# right_revision1_2.net
KiCad netlist of a schematic drawn in EAGLE
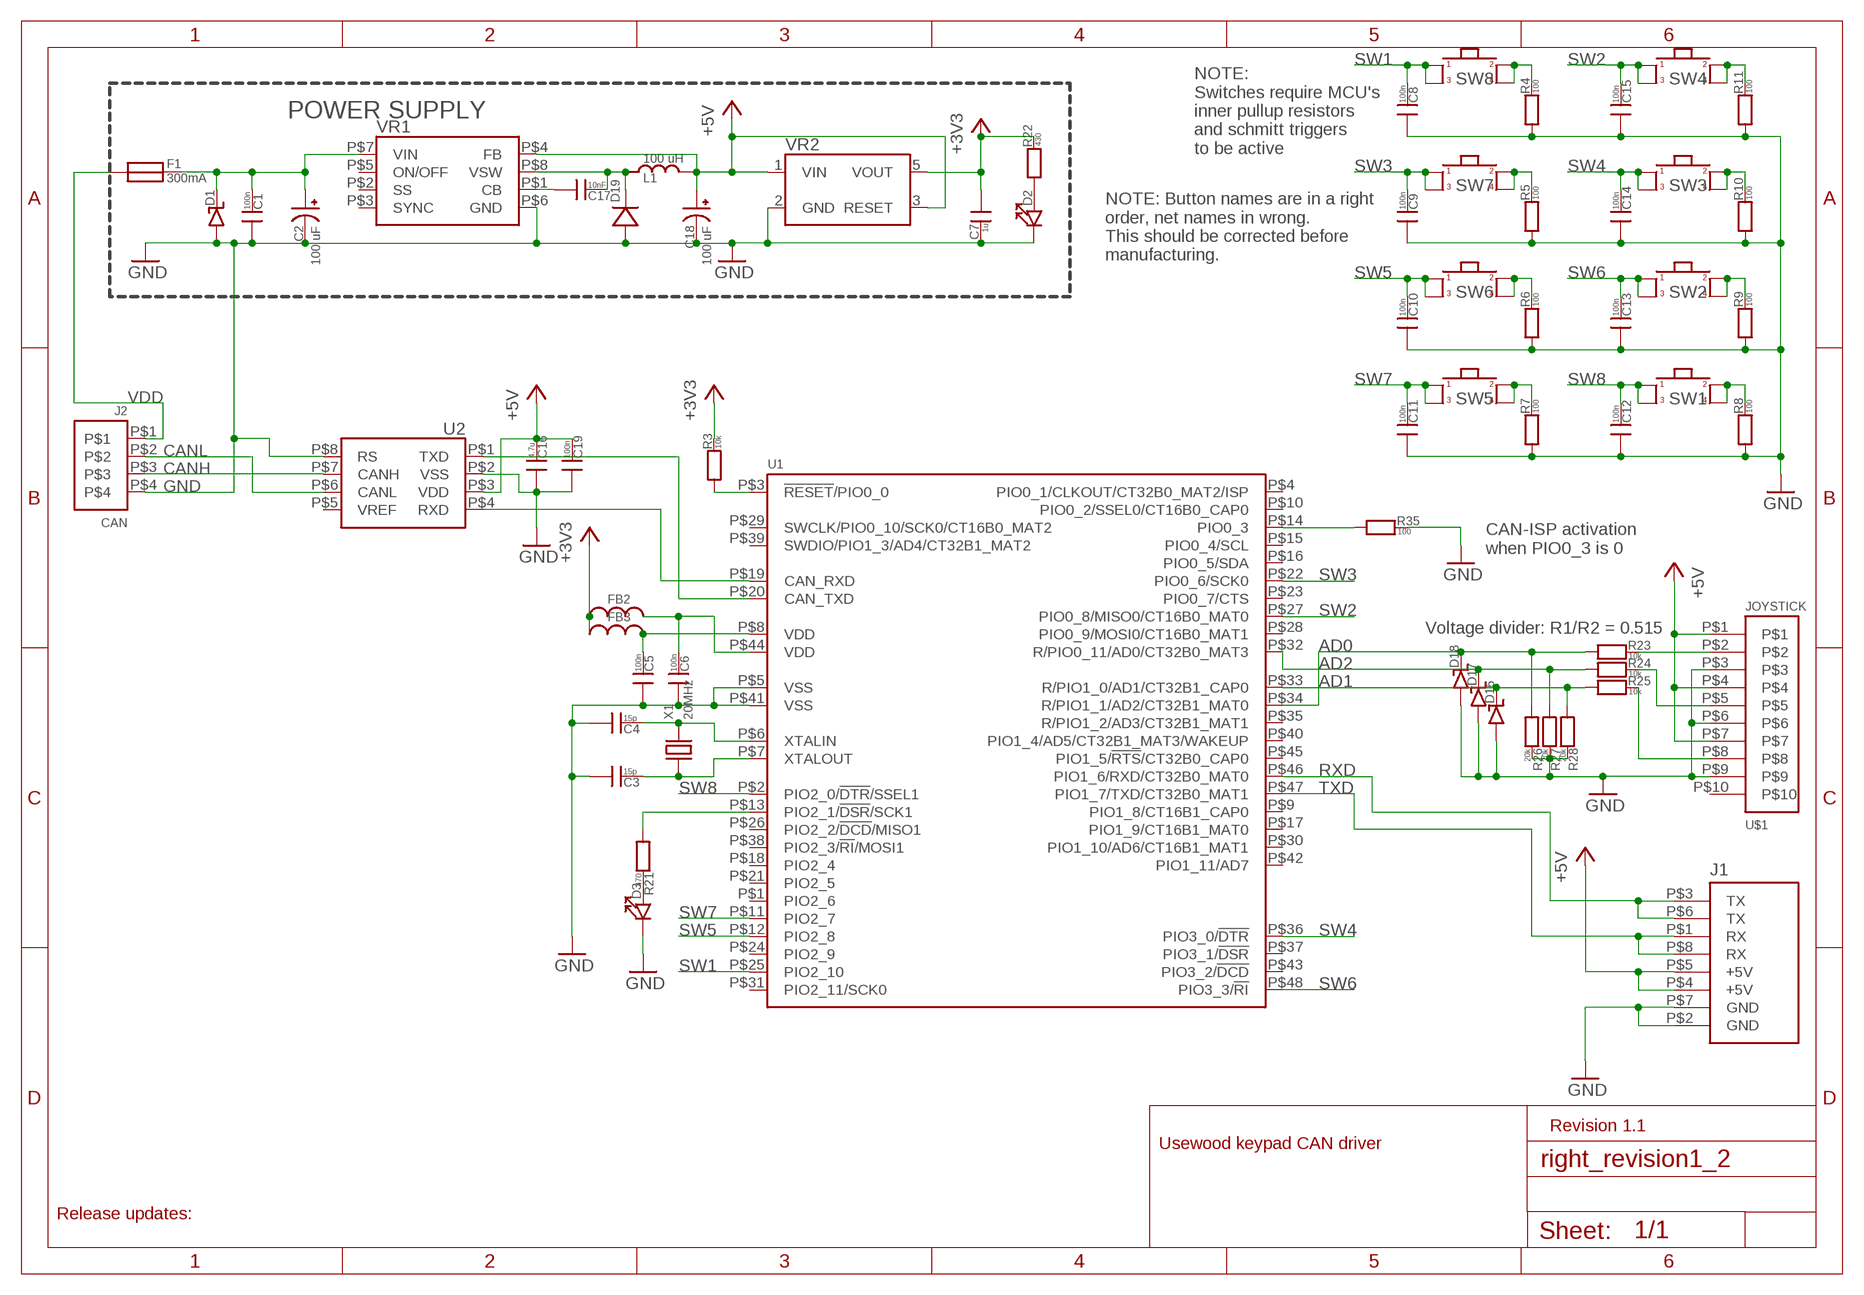
[diagram p0: schematic, sheet 1]

(export (version "E")
  (design (tool "Eeschema 10.0.6"))
  (components
    (comp (ref "C1")
      (value "100n")
      (footprint "eagle-import:0603_SILKSCREEN")
      (libsource (lib "eagle-import") (part "CAP0603_SILKSCREEN"))
    )
    (comp (ref "C2")
      (value "100 uF")
      (footprint "eagle-import:CAP_POL_SMD_10X10X10MM")
      (libsource (lib "eagle-import") (part "CAP_POLSMD_10X10X10MM"))
    )
    (comp (ref "C3")
      (value "15p")
      (footprint "eagle-import:0603_SILKSCREEN")
      (libsource (lib "eagle-import") (part "CAP0603_SILKSCREEN"))
    )
    (comp (ref "C4")
      (value "15p")
      (footprint "eagle-import:0603_SILKSCREEN")
      (libsource (lib "eagle-import") (part "CAP0603_SILKSCREEN"))
    )
    (comp (ref "C5")
      (value "100n")
      (footprint "eagle-import:0603_SILKSCREEN")
      (libsource (lib "eagle-import") (part "CAP0603_SILKSCREEN"))
    )
    (comp (ref "C6")
      (value "100n")
      (footprint "eagle-import:0603_SILKSCREEN")
      (libsource (lib "eagle-import") (part "CAP0603_SILKSCREEN"))
    )
    (comp (ref "C7")
      (value "1u")
      (footprint "eagle-import:0603_SILKSCREEN")
      (libsource (lib "eagle-import") (part "CAP0603_SILKSCREEN"))
    )
    (comp (ref "C8")
      (value "100n")
      (footprint "eagle-import:0603_SILKSCREEN")
      (libsource (lib "eagle-import") (part "CAP0603_SILKSCREEN"))
    )
    (comp (ref "C9")
      (value "100n")
      (footprint "eagle-import:0603_SILKSCREEN")
      (libsource (lib "eagle-import") (part "CAP0603_SILKSCREEN"))
    )
    (comp (ref "C10")
      (value "100n")
      (footprint "eagle-import:0603_SILKSCREEN")
      (libsource (lib "eagle-import") (part "CAP0603_SILKSCREEN"))
    )
    (comp (ref "C11")
      (value "100n")
      (footprint "eagle-import:0603_SILKSCREEN")
      (libsource (lib "eagle-import") (part "CAP0603_SILKSCREEN"))
    )
    (comp (ref "C12")
      (value "100n")
      (footprint "eagle-import:0603_SILKSCREEN")
      (libsource (lib "eagle-import") (part "CAP0603_SILKSCREEN"))
    )
    (comp (ref "C13")
      (value "100n")
      (footprint "eagle-import:0603_SILKSCREEN")
      (libsource (lib "eagle-import") (part "CAP0603_SILKSCREEN"))
    )
    (comp (ref "C14")
      (value "100n")
      (footprint "eagle-import:0603_SILKSCREEN")
      (libsource (lib "eagle-import") (part "CAP0603_SILKSCREEN"))
    )
    (comp (ref "C15")
      (value "100n")
      (footprint "eagle-import:0603_SILKSCREEN")
      (libsource (lib "eagle-import") (part "CAP0603_SILKSCREEN"))
    )
    (comp (ref "C16")
      (value "4.7u")
      (footprint "eagle-import:0603_SILKSCREEN")
      (libsource (lib "eagle-import") (part "CAP0603_SILKSCREEN"))
    )
    (comp (ref "C17")
      (value "10nF")
      (footprint "eagle-import:0603_SILKSCREEN")
      (libsource (lib "eagle-import") (part "CAP0603_SILKSCREEN"))
    )
    (comp (ref "C18")
      (value "100 uF")
      (footprint "eagle-import:CAP_POL_SMD_10X10X10MM")
      (libsource (lib "eagle-import") (part "CAP_POLSMD_10X10X10MM"))
    )
    (comp (ref "C19")
      (value "100n")
      (footprint "eagle-import:0603_SILKSCREEN")
      (libsource (lib "eagle-import") (part "CAP0603_SILKSCREEN"))
    )
    (comp (ref "D1")
      (value "DIODE_TVSDO-214AA")
      (footprint "eagle-import:DO-214AB")
      (libsource (lib "eagle-import") (part "DIODE_TVSDO-214AA"))
    )
    (comp (ref "D2")
      (value "LED0603_SILKSCREEN")
      (footprint "eagle-import:0603_SILKSCREEN")
      (libsource (lib "eagle-import") (part "LED0603_SILKSCREEN"))
    )
    (comp (ref "D3")
      (value "LED0603_SILKSCREEN")
      (footprint "eagle-import:0603_SILKSCREEN")
      (libsource (lib "eagle-import") (part "LED0603_SILKSCREEN"))
    )
    (comp (ref "D16")
      (value "DIODE_ZENERSDO123")
      (footprint "eagle-import:SOD123")
      (libsource (lib "eagle-import") (part "DIODE_ZENERSDO123"))
    )
    (comp (ref "D17")
      (value "DIODE_ZENERSDO123")
      (footprint "eagle-import:SOD123")
      (libsource (lib "eagle-import") (part "DIODE_ZENERSDO123"))
    )
    (comp (ref "D18")
      (value "DIODE_ZENERSDO123")
      (footprint "eagle-import:SOD123")
      (libsource (lib "eagle-import") (part "DIODE_ZENERSDO123"))
    )
    (comp (ref "D19")
      (value "DIODEDO219AB")
      (footprint "eagle-import:DO219AB")
      (libsource (lib "eagle-import") (part "DIODEDO219AB"))
    )
    (comp (ref "F1")
      (value "300mA")
      (footprint "eagle-import:FUSE_100MA")
      (libsource (lib "eagle-import") (part "FUSE100MA"))
    )
    (comp (ref "FB2")
      (value "FERRITE0603_SILKSCREEN")
      (footprint "eagle-import:0603_SILKSCREEN")
      (libsource (lib "eagle-import") (part "FERRITE0603_SILKSCREEN"))
    )
    (comp (ref "FB3")
      (value "FERRITE0603_SILKSCREEN")
      (footprint "eagle-import:0603_SILKSCREEN")
      (libsource (lib "eagle-import") (part "FERRITE0603_SILKSCREEN"))
    )
    (comp (ref "J1")
      (value "HEADER_USART_2_TH")
      (footprint "eagle-import:HEADER_USART_2_TH")
      (libsource (lib "eagle-import") (part "HEADER_USART_2_TH"))
    )
    (comp (ref "J2")
      (value "CAN")
      (footprint "eagle-import:MOLEX_MICRO-FIT_4WAY")
      (libsource (lib "eagle-import") (part "MOLEX_MICRO-FIT_4WAYTH"))
    )
    (comp (ref "L1")
      (value "100 uH")
      (footprint "eagle-import:INDUCTOR_BOURNS_10X13X5MM")
      (libsource (lib "eagle-import") (part "INDUCTORBOURNS_10X13X5MM"))
    )
    (comp (ref "R3")
      (value "10k")
      (footprint "eagle-import:0603_SILKSCREEN")
      (libsource (lib "eagle-import") (part "RES0604_SILKSCREEN"))
    )
    (comp (ref "R4")
      (value "100")
      (footprint "eagle-import:0603_SILKSCREEN")
      (libsource (lib "eagle-import") (part "RES0604_SILKSCREEN"))
    )
    (comp (ref "R5")
      (value "100")
      (footprint "eagle-import:0603_SILKSCREEN")
      (libsource (lib "eagle-import") (part "RES0604_SILKSCREEN"))
    )
    (comp (ref "R6")
      (value "100")
      (footprint "eagle-import:0603_SILKSCREEN")
      (libsource (lib "eagle-import") (part "RES0604_SILKSCREEN"))
    )
    (comp (ref "R7")
      (value "100")
      (footprint "eagle-import:0603_SILKSCREEN")
      (libsource (lib "eagle-import") (part "RES0604_SILKSCREEN"))
    )
    (comp (ref "R8")
      (value "100")
      (footprint "eagle-import:0603_SILKSCREEN")
      (libsource (lib "eagle-import") (part "RES0604_SILKSCREEN"))
    )
    (comp (ref "R9")
      (value "100")
      (footprint "eagle-import:0603_SILKSCREEN")
      (libsource (lib "eagle-import") (part "RES0604_SILKSCREEN"))
    )
    (comp (ref "R10")
      (value "100")
      (footprint "eagle-import:0603_SILKSCREEN")
      (libsource (lib "eagle-import") (part "RES0604_SILKSCREEN"))
    )
    (comp (ref "R11")
      (value "100")
      (footprint "eagle-import:0603_SILKSCREEN")
      (libsource (lib "eagle-import") (part "RES0604_SILKSCREEN"))
    )
    (comp (ref "R21")
      (value "470")
      (footprint "eagle-import:0603_SILKSCREEN")
      (libsource (lib "eagle-import") (part "RES0604_SILKSCREEN"))
    )
    (comp (ref "R22")
      (value "430")
      (footprint "eagle-import:0603_SILKSCREEN")
      (libsource (lib "eagle-import") (part "RES0604_SILKSCREEN"))
    )
    (comp (ref "R23")
      (value "10k")
      (footprint "eagle-import:0603_SILKSCREEN")
      (libsource (lib "eagle-import") (part "RES0604_SILKSCREEN"))
    )
    (comp (ref "R24")
      (value "10k")
      (footprint "eagle-import:0603_SILKSCREEN")
      (libsource (lib "eagle-import") (part "RES0604_SILKSCREEN"))
    )
    (comp (ref "R25")
      (value "10k")
      (footprint "eagle-import:0603_SILKSCREEN")
      (libsource (lib "eagle-import") (part "RES0604_SILKSCREEN"))
    )
    (comp (ref "R26")
      (value "20k")
      (footprint "eagle-import:0603_SILKSCREEN")
      (libsource (lib "eagle-import") (part "RES0604_SILKSCREEN"))
    )
    (comp (ref "R27")
      (value "20k")
      (footprint "eagle-import:0603_SILKSCREEN")
      (libsource (lib "eagle-import") (part "RES0604_SILKSCREEN"))
    )
    (comp (ref "R28")
      (value "20k")
      (footprint "eagle-import:0603_SILKSCREEN")
      (libsource (lib "eagle-import") (part "RES0604_SILKSCREEN"))
    )
    (comp (ref "R35")
      (value "100")
      (footprint "eagle-import:0603_SILKSCREEN")
      (libsource (lib "eagle-import") (part "RES0604_SILKSCREEN"))
    )
    (comp (ref "SW1")
      (value "SWITCH12X12MM_CENTER_HOLE")
      (footprint "eagle-import:SWITCH_12X12MM_CENTER_HOLE")
      (libsource (lib "eagle-import") (part "SWITCH12X12MM_CENTER_HOLE"))
    )
    (comp (ref "SW2")
      (value "SWITCH12X12MM_CENTER_HOLE")
      (footprint "eagle-import:SWITCH_12X12MM_CENTER_HOLE")
      (libsource (lib "eagle-import") (part "SWITCH12X12MM_CENTER_HOLE"))
    )
    (comp (ref "SW3")
      (value "SWITCH12X12MM_CENTER_HOLE")
      (footprint "eagle-import:SWITCH_12X12MM_CENTER_HOLE")
      (libsource (lib "eagle-import") (part "SWITCH12X12MM_CENTER_HOLE"))
    )
    (comp (ref "SW4")
      (value "SWITCH12X12MM_CENTER_HOLE")
      (footprint "eagle-import:SWITCH_12X12MM_CENTER_HOLE")
      (libsource (lib "eagle-import") (part "SWITCH12X12MM_CENTER_HOLE"))
    )
    (comp (ref "SW5")
      (value "SWITCH12X12MM_CENTER_HOLE")
      (footprint "eagle-import:SWITCH_12X12MM_CENTER_HOLE")
      (libsource (lib "eagle-import") (part "SWITCH12X12MM_CENTER_HOLE"))
    )
    (comp (ref "SW6")
      (value "SWITCH12X12MM_CENTER_HOLE")
      (footprint "eagle-import:SWITCH_12X12MM_CENTER_HOLE")
      (libsource (lib "eagle-import") (part "SWITCH12X12MM_CENTER_HOLE"))
    )
    (comp (ref "SW7")
      (value "SWITCH12X12MM_CENTER_HOLE")
      (footprint "eagle-import:SWITCH_12X12MM_CENTER_HOLE")
      (libsource (lib "eagle-import") (part "SWITCH12X12MM_CENTER_HOLE"))
    )
    (comp (ref "SW8")
      (value "SWITCH12X12MM_CENTER_HOLE")
      (footprint "eagle-import:SWITCH_12X12MM_CENTER_HOLE")
      (libsource (lib "eagle-import") (part "SWITCH12X12MM_CENTER_HOLE"))
    )
    (comp (ref "U$1")
      (value "JOYSTICK")
      (footprint "eagle-import:MOLEX-MICRO-FIT_10WAY")
      (libsource (lib "eagle-import") (part "MOLEX_MICRO-FIT_10WAYTH"))
    )
    (comp (ref "U1")
      (value "LPC11C14_QFP48")
      (footprint "eagle-import:QFP48")
      (libsource (lib "eagle-import") (part "LPC11C14_QFP48"))
    )
    (comp (ref "U2")
      (value "MCP2551_SOIC8")
      (footprint "eagle-import:SOIC8")
      (libsource (lib "eagle-import") (part "MCP2551_SOIC8"))
    )
    (comp (ref "VR1")
      (value "LM2671SOIC8")
      (footprint "eagle-import:SOIC8")
      (libsource (lib "eagle-import") (part "LM2671SOIC8"))
    )
    (comp (ref "VR2")
      (value "LP2985SOP5")
      (footprint "eagle-import:SOP5")
      (libsource (lib "eagle-import") (part "LP2985SOP5"))
    )
    (comp (ref "X1")
      (value "20MHz")
      (footprint "eagle-import:XTAL_SMD_5X3.2")
      (libsource (lib "eagle-import") (part "XTALSMD_5X3.2"))
    )
  )
  (nets
    (net (code "1") (name "+3V3") (class "Default")
      (node (ref "C7") (pin "0") (pinfunction "P$1_0") (pintype "bidirectional"))
      (node (ref "FB2") (pin "0") (pinfunction "P$1_0") (pintype "bidirectional"))
      (node (ref "FB3") (pin "0") (pinfunction "P$1_0") (pintype "bidirectional"))
      (node (ref "R22") (pin "1") (pinfunction "P$2_1") (pintype "bidirectional"))
      (node (ref "R3") (pin "1") (pinfunction "P$2_1") (pintype "bidirectional"))
      (node (ref "VR2") (pin "5") (pinfunction "VOUT_5") (pintype "bidirectional"))
    )
    (net (code "2") (name "+5V") (class "Default")
      (node (ref "C16") (pin "1") (pinfunction "P$2_1") (pintype "bidirectional"))
      (node (ref "C18") (pin "+") (pinfunction "+_+") (pintype "bidirectional"))
      (node (ref "C19") (pin "1") (pinfunction "P$2_1") (pintype "bidirectional"))
      (node (ref "J1") (pin "P$4") (pinfunction "+5V_P$4") (pintype "bidirectional"))
      (node (ref "J1") (pin "P$5") (pinfunction "+5V_P$5") (pintype "bidirectional"))
      (node (ref "L1") (pin "P$2") (pinfunction "P$2_P$2") (pintype "bidirectional"))
      (node (ref "U$1") (pin "P$1") (pinfunction "P$1_P$1") (pintype "bidirectional"))
      (node (ref "U$1") (pin "P$4") (pinfunction "P$4_P$4") (pintype "bidirectional"))
      (node (ref "U$1") (pin "P$7") (pinfunction "P$7_P$7") (pintype "bidirectional"))
      (node (ref "U2") (pin "P$3") (pinfunction "VDD_P$3") (pintype "bidirectional"))
      (node (ref "VR1") (pin "P$4") (pinfunction "FB_P$4") (pintype "bidirectional"))
      (node (ref "VR2") (pin "1") (pinfunction "VIN_1") (pintype "bidirectional"))
      (node (ref "VR2") (pin "3") (pinfunction "RESET_3") (pintype "bidirectional"))
    )
    (net (code "3") (name "/AD0") (class "Default")
      (node (ref "D18") (pin "P$2") (pinfunction "N_P$2") (pintype "bidirectional"))
      (node (ref "R23") (pin "0") (pinfunction "P$1_0") (pintype "bidirectional"))
      (node (ref "R26") (pin "0") (pinfunction "P$1_0") (pintype "bidirectional"))
      (node (ref "U1") (pin "P$34") (pinfunction "R/PIO1_1/AD2/CT32B1_MAT0_P$34") (pintype "bidirectional"))
    )
    (net (code "4") (name "/AD1") (class "Default")
      (node (ref "D16") (pin "P$2") (pinfunction "N_P$2") (pintype "bidirectional"))
      (node (ref "R25") (pin "0") (pinfunction "P$1_0") (pintype "bidirectional"))
      (node (ref "R28") (pin "0") (pinfunction "P$1_0") (pintype "bidirectional"))
      (node (ref "U1") (pin "P$33") (pinfunction "R/PIO1_0/AD1/CT32B1_CAP0_P$33") (pintype "bidirectional"))
    )
    (net (code "5") (name "/AD2") (class "Default")
      (node (ref "D17") (pin "P$2") (pinfunction "N_P$2") (pintype "bidirectional"))
      (node (ref "R24") (pin "0") (pinfunction "P$1_0") (pintype "bidirectional"))
      (node (ref "R27") (pin "0") (pinfunction "P$1_0") (pintype "bidirectional"))
      (node (ref "U1") (pin "P$32") (pinfunction "R/PIO0_11/AD0/CT32B0_MAT3_P$32") (pintype "bidirectional"))
    )
    (net (code "6") (name "/CANH") (class "Default")
      (node (ref "J2") (pin "P$3") (pinfunction "P$3_P$3") (pintype "bidirectional"))
      (node (ref "U2") (pin "P$7") (pinfunction "CANH_P$7") (pintype "bidirectional"))
    )
    (net (code "7") (name "/CANL") (class "Default")
      (node (ref "J2") (pin "P$2") (pinfunction "P$2_P$2") (pintype "bidirectional"))
      (node (ref "U2") (pin "P$6") (pinfunction "CANL_P$6") (pintype "bidirectional"))
    )
    (net (code "8") (name "/RXD") (class "Default")
      (node (ref "J1") (pin "P$3") (pinfunction "TX_P$3") (pintype "bidirectional"))
      (node (ref "J1") (pin "P$6") (pinfunction "TX_P$6") (pintype "bidirectional"))
      (node (ref "U1") (pin "P$46") (pinfunction "PIO1_6/RXD/CT32B0_MAT0_P$46") (pintype "bidirectional"))
    )
    (net (code "9") (name "/SW1") (class "Default")
      (node (ref "C8") (pin "1") (pinfunction "P$2_1") (pintype "bidirectional"))
      (node (ref "SW8") (pin "P$1") (pinfunction "P$1_P$1") (pintype "bidirectional"))
      (node (ref "SW8") (pin "P$2") (pinfunction "P$3_P$2") (pintype "bidirectional"))
      (node (ref "U1") (pin "P$25") (pinfunction "PIO2_10_P$25") (pintype "bidirectional"))
    )
    (net (code "10") (name "/SW2") (class "Default")
      (node (ref "C15") (pin "1") (pinfunction "P$2_1") (pintype "bidirectional"))
      (node (ref "SW4") (pin "P$1") (pinfunction "P$1_P$1") (pintype "bidirectional"))
      (node (ref "SW4") (pin "P$2") (pinfunction "P$3_P$2") (pintype "bidirectional"))
      (node (ref "U1") (pin "P$27") (pinfunction "PIO0_8/MISO0/CT16B0_MAT0_P$27") (pintype "bidirectional"))
    )
    (net (code "11") (name "/SW3") (class "Default")
      (node (ref "C9") (pin "1") (pinfunction "P$2_1") (pintype "bidirectional"))
      (node (ref "SW7") (pin "P$1") (pinfunction "P$1_P$1") (pintype "bidirectional"))
      (node (ref "SW7") (pin "P$2") (pinfunction "P$3_P$2") (pintype "bidirectional"))
      (node (ref "U1") (pin "P$22") (pinfunction "PIO0_6/SCK0_P$22") (pintype "bidirectional"))
    )
    (net (code "12") (name "/SW4") (class "Default")
      (node (ref "C14") (pin "1") (pinfunction "P$2_1") (pintype "bidirectional"))
      (node (ref "SW3") (pin "P$1") (pinfunction "P$1_P$1") (pintype "bidirectional"))
      (node (ref "SW3") (pin "P$2") (pinfunction "P$3_P$2") (pintype "bidirectional"))
      (node (ref "U1") (pin "P$36") (pinfunction "PIO3_0/~{DTR}_P$36") (pintype "bidirectional"))
    )
    (net (code "13") (name "/SW5") (class "Default")
      (node (ref "C10") (pin "1") (pinfunction "P$2_1") (pintype "bidirectional"))
      (node (ref "SW6") (pin "P$1") (pinfunction "P$1_P$1") (pintype "bidirectional"))
      (node (ref "SW6") (pin "P$2") (pinfunction "P$3_P$2") (pintype "bidirectional"))
      (node (ref "U1") (pin "P$12") (pinfunction "PIO2_8_P$12") (pintype "bidirectional"))
    )
    (net (code "14") (name "/SW6") (class "Default")
      (node (ref "C13") (pin "1") (pinfunction "P$2_1") (pintype "bidirectional"))
      (node (ref "SW2") (pin "P$1") (pinfunction "P$1_P$1") (pintype "bidirectional"))
      (node (ref "SW2") (pin "P$2") (pinfunction "P$3_P$2") (pintype "bidirectional"))
      (node (ref "U1") (pin "P$48") (pinfunction "PIO3_3/~{RI}_P$48") (pintype "bidirectional"))
    )
    (net (code "15") (name "/SW7") (class "Default")
      (node (ref "C11") (pin "1") (pinfunction "P$2_1") (pintype "bidirectional"))
      (node (ref "SW5") (pin "P$1") (pinfunction "P$1_P$1") (pintype "bidirectional"))
      (node (ref "SW5") (pin "P$2") (pinfunction "P$3_P$2") (pintype "bidirectional"))
      (node (ref "U1") (pin "P$11") (pinfunction "PIO2_7_P$11") (pintype "bidirectional"))
    )
    (net (code "16") (name "/SW8") (class "Default")
      (node (ref "C12") (pin "1") (pinfunction "P$2_1") (pintype "bidirectional"))
      (node (ref "SW1") (pin "P$1") (pinfunction "P$1_P$1") (pintype "bidirectional"))
      (node (ref "SW1") (pin "P$2") (pinfunction "P$3_P$2") (pintype "bidirectional"))
      (node (ref "U1") (pin "P$2") (pinfunction "PIO2_0/~{DTR}/SSEL1_P$2") (pintype "bidirectional"))
    )
    (net (code "17") (name "/TXD") (class "Default")
      (node (ref "J1") (pin "P$1") (pinfunction "RX_P$1") (pintype "bidirectional"))
      (node (ref "J1") (pin "P$8") (pinfunction "RX_P$8") (pintype "bidirectional"))
      (node (ref "U1") (pin "P$47") (pinfunction "PIO1_7/TXD/CT32B0_MAT1_P$47") (pintype "bidirectional"))
    )
    (net (code "18") (name "/VDD") (class "Default")
      (node (ref "F1") (pin "P$1") (pinfunction "P$1_P$1") (pintype "bidirectional"))
      (node (ref "J2") (pin "P$1") (pinfunction "P$1_P$1") (pintype "bidirectional"))
    )
    (net (code "19") (name "GND") (class "Default")
      (node (ref "C1") (pin "0") (pinfunction "P$1_0") (pintype "bidirectional"))
      (node (ref "C10") (pin "0") (pinfunction "P$1_0") (pintype "bidirectional"))
      (node (ref "C11") (pin "0") (pinfunction "P$1_0") (pintype "bidirectional"))
      (node (ref "C12") (pin "0") (pinfunction "P$1_0") (pintype "bidirectional"))
      (node (ref "C13") (pin "0") (pinfunction "P$1_0") (pintype "bidirectional"))
      (node (ref "C14") (pin "0") (pinfunction "P$1_0") (pintype "bidirectional"))
      (node (ref "C15") (pin "0") (pinfunction "P$1_0") (pintype "bidirectional"))
      (node (ref "C16") (pin "0") (pinfunction "P$1_0") (pintype "bidirectional"))
      (node (ref "C18") (pin "-") (pinfunction "-_-") (pintype "bidirectional"))
      (node (ref "C19") (pin "0") (pinfunction "P$1_0") (pintype "bidirectional"))
      (node (ref "C2") (pin "-") (pinfunction "-_-") (pintype "bidirectional"))
      (node (ref "C3") (pin "0") (pinfunction "P$1_0") (pintype "bidirectional"))
      (node (ref "C4") (pin "0") (pinfunction "P$1_0") (pintype "bidirectional"))
      (node (ref "C5") (pin "0") (pinfunction "P$1_0") (pintype "bidirectional"))
      (node (ref "C6") (pin "0") (pinfunction "P$1_0") (pintype "bidirectional"))
      (node (ref "C7") (pin "1") (pinfunction "P$2_1") (pintype "bidirectional"))
      (node (ref "C8") (pin "0") (pinfunction "P$1_0") (pintype "bidirectional"))
      (node (ref "C9") (pin "0") (pinfunction "P$1_0") (pintype "bidirectional"))
      (node (ref "D1") (pin "P$1") (pinfunction "P_P$1") (pintype "bidirectional"))
      (node (ref "D16") (pin "P$1") (pinfunction "P_P$1") (pintype "bidirectional"))
      (node (ref "D17") (pin "P$1") (pinfunction "P_P$1") (pintype "bidirectional"))
      (node (ref "D18") (pin "P$1") (pinfunction "P_P$1") (pintype "bidirectional"))
      (node (ref "D19") (pin "P$1") (pinfunction "P_P$1") (pintype "bidirectional"))
      (node (ref "D2") (pin "1") (pinfunction "1_1") (pintype "bidirectional"))
      (node (ref "D3") (pin "1") (pinfunction "1_1") (pintype "bidirectional"))
      (node (ref "J1") (pin "P$2") (pinfunction "GND_P$2") (pintype "bidirectional"))
      (node (ref "J1") (pin "P$7") (pinfunction "GND_P$7") (pintype "bidirectional"))
      (node (ref "J2") (pin "P$4") (pinfunction "P$4_P$4") (pintype "bidirectional"))
      (node (ref "R10") (pin "0") (pinfunction "P$1_0") (pintype "bidirectional"))
      (node (ref "R11") (pin "0") (pinfunction "P$1_0") (pintype "bidirectional"))
      (node (ref "R26") (pin "1") (pinfunction "P$2_1") (pintype "bidirectional"))
      (node (ref "R27") (pin "1") (pinfunction "P$2_1") (pintype "bidirectional"))
      (node (ref "R28") (pin "1") (pinfunction "P$2_1") (pintype "bidirectional"))
      (node (ref "R35") (pin "1") (pinfunction "P$2_1") (pintype "bidirectional"))
      (node (ref "R4") (pin "0") (pinfunction "P$1_0") (pintype "bidirectional"))
      (node (ref "R5") (pin "0") (pinfunction "P$1_0") (pintype "bidirectional"))
      (node (ref "R6") (pin "0") (pinfunction "P$1_0") (pintype "bidirectional"))
      (node (ref "R7") (pin "0") (pinfunction "P$1_0") (pintype "bidirectional"))
      (node (ref "R8") (pin "0") (pinfunction "P$1_0") (pintype "bidirectional"))
      (node (ref "R9") (pin "0") (pinfunction "P$1_0") (pintype "bidirectional"))
      (node (ref "U$1") (pin "P$3") (pinfunction "P$3_P$3") (pintype "bidirectional"))
      (node (ref "U$1") (pin "P$6") (pinfunction "P$6_P$6") (pintype "bidirectional"))
      (node (ref "U$1") (pin "P$9") (pinfunction "P$9_P$9") (pintype "bidirectional"))
      (node (ref "U1") (pin "P$41") (pinfunction "VSS_P$41") (pintype "bidirectional"))
      (node (ref "U1") (pin "P$5") (pinfunction "VSS_P$5") (pintype "bidirectional"))
      (node (ref "U2") (pin "P$2") (pinfunction "VSS_P$2") (pintype "bidirectional"))
      (node (ref "U2") (pin "P$8") (pinfunction "RS_P$8") (pintype "bidirectional"))
      (node (ref "VR1") (pin "P$6") (pinfunction "GND_P$6") (pintype "bidirectional"))
      (node (ref "VR2") (pin "2") (pinfunction "GND_2") (pintype "bidirectional"))
    )
    (net (code "20") (name "Net-(C1-P$2)") (class "Default")
      (node (ref "C1") (pin "1") (pinfunction "P$2_1") (pintype "bidirectional"))
      (node (ref "C2") (pin "+") (pinfunction "+_+") (pintype "bidirectional"))
      (node (ref "D1") (pin "P$2") (pinfunction "N_P$2") (pintype "bidirectional"))
      (node (ref "F1") (pin "P$2") (pinfunction "P$2_P$2") (pintype "bidirectional"))
      (node (ref "VR1") (pin "P$7") (pinfunction "VIN_P$7") (pintype "bidirectional"))
    )
    (net (code "21") (name "Net-(C3-P$2)") (class "Default")
      (node (ref "C3") (pin "1") (pinfunction "P$2_1") (pintype "bidirectional"))
      (node (ref "U1") (pin "P$7") (pinfunction "XTALOUT_P$7") (pintype "bidirectional"))
      (node (ref "X1") (pin "P$1") (pinfunction "P$1_P$1") (pintype "bidirectional"))
    )
    (net (code "22") (name "Net-(C4-P$2)") (class "Default")
      (node (ref "C4") (pin "1") (pinfunction "P$2_1") (pintype "bidirectional"))
      (node (ref "U1") (pin "P$6") (pinfunction "XTALIN_P$6") (pintype "bidirectional"))
      (node (ref "X1") (pin "P$2") (pinfunction "P$2_P$2") (pintype "bidirectional"))
    )
    (net (code "23") (name "Net-(C5-P$2)") (class "Default")
      (node (ref "C5") (pin "1") (pinfunction "P$2_1") (pintype "bidirectional"))
      (node (ref "FB3") (pin "1") (pinfunction "P$2_1") (pintype "bidirectional"))
      (node (ref "U1") (pin "P$8") (pinfunction "VDD_P$8") (pintype "bidirectional"))
    )
    (net (code "24") (name "Net-(C6-P$2)") (class "Default")
      (node (ref "C6") (pin "1") (pinfunction "P$2_1") (pintype "bidirectional"))
      (node (ref "FB2") (pin "1") (pinfunction "P$2_1") (pintype "bidirectional"))
      (node (ref "U1") (pin "P$44") (pinfunction "VDD_P$44") (pintype "bidirectional"))
    )
    (net (code "25") (name "Net-(C17-P$1)") (class "Default")
      (node (ref "C17") (pin "0") (pinfunction "P$1_0") (pintype "bidirectional"))
      (node (ref "VR1") (pin "P$1") (pinfunction "CB_P$1") (pintype "bidirectional"))
    )
    (net (code "26") (name "Net-(C17-P$2)") (class "Default")
      (node (ref "C17") (pin "1") (pinfunction "P$2_1") (pintype "bidirectional"))
      (node (ref "D19") (pin "P$2") (pinfunction "N_P$2") (pintype "bidirectional"))
      (node (ref "L1") (pin "P$1") (pinfunction "P$1_P$1") (pintype "bidirectional"))
      (node (ref "VR1") (pin "P$8") (pinfunction "VSW_P$8") (pintype "bidirectional"))
    )
    (net (code "27") (name "Net-(R3-P$1)") (class "Default")
      (node (ref "R3") (pin "0") (pinfunction "P$1_0") (pintype "bidirectional"))
      (node (ref "U1") (pin "P$3") (pinfunction "~{RESET}/PIO0_0_P$3") (pintype "bidirectional"))
    )
    (net (code "28") (name "Net-(R4-P$2)") (class "Default")
      (node (ref "R4") (pin "1") (pinfunction "P$2_1") (pintype "bidirectional"))
      (node (ref "SW8") (pin "P$3") (pinfunction "P$2_P$3") (pintype "bidirectional"))
      (node (ref "SW8") (pin "P$4") (pinfunction "P$4_P$4") (pintype "bidirectional"))
    )
    (net (code "29") (name "Net-(R5-P$2)") (class "Default")
      (node (ref "R5") (pin "1") (pinfunction "P$2_1") (pintype "bidirectional"))
      (node (ref "SW7") (pin "P$3") (pinfunction "P$2_P$3") (pintype "bidirectional"))
      (node (ref "SW7") (pin "P$4") (pinfunction "P$4_P$4") (pintype "bidirectional"))
    )
    (net (code "30") (name "Net-(R6-P$2)") (class "Default")
      (node (ref "R6") (pin "1") (pinfunction "P$2_1") (pintype "bidirectional"))
      (node (ref "SW6") (pin "P$3") (pinfunction "P$2_P$3") (pintype "bidirectional"))
      (node (ref "SW6") (pin "P$4") (pinfunction "P$4_P$4") (pintype "bidirectional"))
    )
    (net (code "31") (name "Net-(R7-P$2)") (class "Default")
      (node (ref "R7") (pin "1") (pinfunction "P$2_1") (pintype "bidirectional"))
      (node (ref "SW5") (pin "P$3") (pinfunction "P$2_P$3") (pintype "bidirectional"))
      (node (ref "SW5") (pin "P$4") (pinfunction "P$4_P$4") (pintype "bidirectional"))
    )
    (net (code "32") (name "Net-(R8-P$2)") (class "Default")
      (node (ref "R8") (pin "1") (pinfunction "P$2_1") (pintype "bidirectional"))
      (node (ref "SW1") (pin "P$3") (pinfunction "P$2_P$3") (pintype "bidirectional"))
      (node (ref "SW1") (pin "P$4") (pinfunction "P$4_P$4") (pintype "bidirectional"))
    )
    (net (code "33") (name "Net-(R9-P$2)") (class "Default")
      (node (ref "R9") (pin "1") (pinfunction "P$2_1") (pintype "bidirectional"))
      (node (ref "SW2") (pin "P$3") (pinfunction "P$2_P$3") (pintype "bidirectional"))
      (node (ref "SW2") (pin "P$4") (pinfunction "P$4_P$4") (pintype "bidirectional"))
    )
    (net (code "34") (name "Net-(R10-P$2)") (class "Default")
      (node (ref "R10") (pin "1") (pinfunction "P$2_1") (pintype "bidirectional"))
      (node (ref "SW3") (pin "P$3") (pinfunction "P$2_P$3") (pintype "bidirectional"))
      (node (ref "SW3") (pin "P$4") (pinfunction "P$4_P$4") (pintype "bidirectional"))
    )
    (net (code "35") (name "Net-(R11-P$2)") (class "Default")
      (node (ref "R11") (pin "1") (pinfunction "P$2_1") (pintype "bidirectional"))
      (node (ref "SW4") (pin "P$3") (pinfunction "P$2_P$3") (pintype "bidirectional"))
      (node (ref "SW4") (pin "P$4") (pinfunction "P$4_P$4") (pintype "bidirectional"))
    )
    (net (code "36") (name "Net-(R21-P$1)") (class "Default")
      (node (ref "R21") (pin "0") (pinfunction "P$1_0") (pintype "bidirectional"))
      (node (ref "U1") (pin "P$13") (pinfunction "PIO2_1/~{DSR}/SCK1_P$13") (pintype "bidirectional"))
    )
    (net (code "37") (name "Net-(R21-P$2)") (class "Default")
      (node (ref "D3") (pin "0") (pinfunction "0_0") (pintype "bidirectional"))
      (node (ref "R21") (pin "1") (pinfunction "P$2_1") (pintype "bidirectional"))
    )
    (net (code "38") (name "Net-(R22-P$1)") (class "Default")
      (node (ref "D2") (pin "0") (pinfunction "0_0") (pintype "bidirectional"))
      (node (ref "R22") (pin "0") (pinfunction "P$1_0") (pintype "bidirectional"))
    )
    (net (code "39") (name "Net-(R23-P$2)") (class "Default")
      (node (ref "R23") (pin "1") (pinfunction "P$2_1") (pintype "bidirectional"))
      (node (ref "U$1") (pin "P$2") (pinfunction "P$2_P$2") (pintype "bidirectional"))
    )
    (net (code "40") (name "Net-(R24-P$2)") (class "Default")
      (node (ref "R24") (pin "1") (pinfunction "P$2_1") (pintype "bidirectional"))
      (node (ref "U$1") (pin "P$5") (pinfunction "P$5_P$5") (pintype "bidirectional"))
    )
    (net (code "41") (name "Net-(R25-P$2)") (class "Default")
      (node (ref "R25") (pin "1") (pinfunction "P$2_1") (pintype "bidirectional"))
      (node (ref "U$1") (pin "P$8") (pinfunction "P$8_P$8") (pintype "bidirectional"))
    )
    (net (code "42") (name "Net-(R35-P$1)") (class "Default")
      (node (ref "R35") (pin "0") (pinfunction "P$1_0") (pintype "bidirectional"))
      (node (ref "U1") (pin "P$14") (pinfunction "PIO0_3_P$14") (pintype "bidirectional"))
    )
    (net (code "43") (name "Net-(U1-CAN_RXD)") (class "Default")
      (node (ref "U1") (pin "P$19") (pinfunction "CAN_RXD_P$19") (pintype "bidirectional"))
      (node (ref "U2") (pin "P$4") (pinfunction "RXD_P$4") (pintype "bidirectional"))
    )
    (net (code "44") (name "Net-(U1-CAN_TXD)") (class "Default")
      (node (ref "U1") (pin "P$20") (pinfunction "CAN_TXD_P$20") (pintype "bidirectional"))
      (node (ref "U2") (pin "P$1") (pinfunction "TXD_P$1") (pintype "bidirectional"))
    )
    (net (code "45") (name "unconnected-(U$1-PadP$10)") (class "Default")
      (node (ref "U$1") (pin "P$10") (pinfunction "P$10_P$10") (pintype "bidirectional"))
    )
    (net (code "46") (name "unconnected-(U1-PIO0_1{slash}CLKOUT{slash}CT32B0_MAT2{slash}ISP-PadP$4)") (class "Default")
      (node (ref "U1") (pin "P$4") (pinfunction "PIO0_1/CLKOUT/CT32B0_MAT2/ISP_P$4") (pintype "bidirectional"))
    )
    (net (code "47") (name "unconnected-(U1-PIO0_2{slash}SSEL0{slash}CT16B0_CAP0-PadP$10)") (class "Default")
      (node (ref "U1") (pin "P$10") (pinfunction "PIO0_2/SSEL0/CT16B0_CAP0_P$10") (pintype "bidirectional"))
    )
    (net (code "48") (name "unconnected-(U1-PIO0_4{slash}SCL-PadP$15)") (class "Default")
      (node (ref "U1") (pin "P$15") (pinfunction "PIO0_4/SCL_P$15") (pintype "bidirectional"))
    )
    (net (code "49") (name "unconnected-(U1-PIO0_5{slash}SDA-PadP$16)") (class "Default")
      (node (ref "U1") (pin "P$16") (pinfunction "PIO0_5/SDA_P$16") (pintype "bidirectional"))
    )
    (net (code "50") (name "unconnected-(U1-PIO0_7{slash}CTS-PadP$23)") (class "Default")
      (node (ref "U1") (pin "P$23") (pinfunction "PIO0_7/CTS_P$23") (pintype "bidirectional"))
    )
    (net (code "51") (name "unconnected-(U1-PIO0_9{slash}MOSI0{slash}CT16B0_MAT1-PadP$28)") (class "Default")
      (node (ref "U1") (pin "P$28") (pinfunction "PIO0_9/MOSI0/CT16B0_MAT1_P$28") (pintype "bidirectional"))
    )
    (net (code "52") (name "unconnected-(U1-PIO1_4{slash}AD5{slash}CT32B1_MAT3{slash}WAKEUP-PadP$40)") (class "Default")
      (node (ref "U1") (pin "P$40") (pinfunction "PIO1_4/AD5/CT32B1_MAT3/WAKEUP_P$40") (pintype "bidirectional"))
    )
    (net (code "53") (name "unconnected-(U1-PIO1_5{slash}~{RTS}{slash}CT32B0_CAP0-PadP$45)") (class "Default")
      (node (ref "U1") (pin "P$45") (pinfunction "PIO1_5/~{RTS}/CT32B0_CAP0_P$45") (pintype "bidirectional"))
    )
    (net (code "54") (name "unconnected-(U1-PIO1_8{slash}CT16B1_CAP0-PadP$9)") (class "Default")
      (node (ref "U1") (pin "P$9") (pinfunction "PIO1_8/CT16B1_CAP0_P$9") (pintype "bidirectional"))
    )
    (net (code "55") (name "unconnected-(U1-PIO1_9{slash}CT16B1_MAT0-PadP$17)") (class "Default")
      (node (ref "U1") (pin "P$17") (pinfunction "PIO1_9/CT16B1_MAT0_P$17") (pintype "bidirectional"))
    )
    (net (code "56") (name "unconnected-(U1-PIO1_10{slash}AD6{slash}CT16B1_MAT1-PadP$30)") (class "Default")
      (node (ref "U1") (pin "P$30") (pinfunction "PIO1_10/AD6/CT16B1_MAT1_P$30") (pintype "bidirectional"))
    )
    (net (code "57") (name "unconnected-(U1-PIO1_11{slash}AD7-PadP$42)") (class "Default")
      (node (ref "U1") (pin "P$42") (pinfunction "PIO1_11/AD7_P$42") (pintype "bidirectional"))
    )
    (net (code "58") (name "unconnected-(U1-PIO2_2{slash}~{DCD}{slash}MISO1-PadP$26)") (class "Default")
      (node (ref "U1") (pin "P$26") (pinfunction "PIO2_2/~{DCD}/MISO1_P$26") (pintype "bidirectional"))
    )
    (net (code "59") (name "unconnected-(U1-PIO2_3{slash}~{RI}{slash}MOSI1-PadP$38)") (class "Default")
      (node (ref "U1") (pin "P$38") (pinfunction "PIO2_3/~{RI}/MOSI1_P$38") (pintype "bidirectional"))
    )
    (net (code "60") (name "unconnected-(U1-PIO2_4-PadP$18)") (class "Default")
      (node (ref "U1") (pin "P$18") (pinfunction "PIO2_4_P$18") (pintype "bidirectional"))
    )
    (net (code "61") (name "unconnected-(U1-PIO2_5-PadP$21)") (class "Default")
      (node (ref "U1") (pin "P$21") (pinfunction "PIO2_5_P$21") (pintype "bidirectional"))
    )
    (net (code "62") (name "unconnected-(U1-PIO2_6-PadP$1)") (class "Default")
      (node (ref "U1") (pin "P$1") (pinfunction "PIO2_6_P$1") (pintype "bidirectional"))
    )
    (net (code "63") (name "unconnected-(U1-PIO2_9-PadP$24)") (class "Default")
      (node (ref "U1") (pin "P$24") (pinfunction "PIO2_9_P$24") (pintype "bidirectional"))
    )
    (net (code "64") (name "unconnected-(U1-PIO2_11{slash}SCK0-PadP$31)") (class "Default")
      (node (ref "U1") (pin "P$31") (pinfunction "PIO2_11/SCK0_P$31") (pintype "bidirectional"))
    )
    (net (code "65") (name "unconnected-(U1-PIO3_1{slash}~{DSR}-PadP$37)") (class "Default")
      (node (ref "U1") (pin "P$37") (pinfunction "PIO3_1/~{DSR}_P$37") (pintype "bidirectional"))
    )
    (net (code "66") (name "unconnected-(U1-PIO3_2{slash}~{DCD}-PadP$43)") (class "Default")
      (node (ref "U1") (pin "P$43") (pinfunction "PIO3_2/~{DCD}_P$43") (pintype "bidirectional"))
    )
    (net (code "67") (name "unconnected-(U1-R{slash}PIO1_2{slash}AD3{slash}CT32B1_MAT1-PadP$35)") (class "Default")
      (node (ref "U1") (pin "P$35") (pinfunction "R/PIO1_2/AD3/CT32B1_MAT1_P$35") (pintype "bidirectional"))
    )
    (net (code "68") (name "unconnected-(U1-SWCLK{slash}PIO0_10{slash}SCK0{slash}CT16B0_MAT2-PadP$29)") (class "Default")
      (node (ref "U1") (pin "P$29") (pinfunction "SWCLK/PIO0_10/SCK0/CT16B0_MAT2_P$29") (pintype "bidirectional"))
    )
    (net (code "69") (name "unconnected-(U1-SWDIO{slash}PIO1_3{slash}AD4{slash}CT32B1_MAT2-PadP$39)") (class "Default")
      (node (ref "U1") (pin "P$39") (pinfunction "SWDIO/PIO1_3/AD4/CT32B1_MAT2_P$39") (pintype "bidirectional"))
    )
    (net (code "70") (name "unconnected-(U2-VREF-PadP$5)") (class "Default")
      (node (ref "U2") (pin "P$5") (pinfunction "VREF_P$5") (pintype "bidirectional"))
    )
    (net (code "71") (name "unconnected-(VR1-ON{slash}OFF-PadP$5)") (class "Default")
      (node (ref "VR1") (pin "P$5") (pinfunction "ON/OFF_P$5") (pintype "bidirectional"))
    )
    (net (code "72") (name "unconnected-(VR1-SS-PadP$2)") (class "Default")
      (node (ref "VR1") (pin "P$2") (pinfunction "SS_P$2") (pintype "bidirectional"))
    )
    (net (code "73") (name "unconnected-(VR1-SYNC-PadP$3)") (class "Default")
      (node (ref "VR1") (pin "P$3") (pinfunction "SYNC_P$3") (pintype "bidirectional"))
    )
  )
)
